# versao1.net
KiCad netlist of a schematic drawn in EAGLE
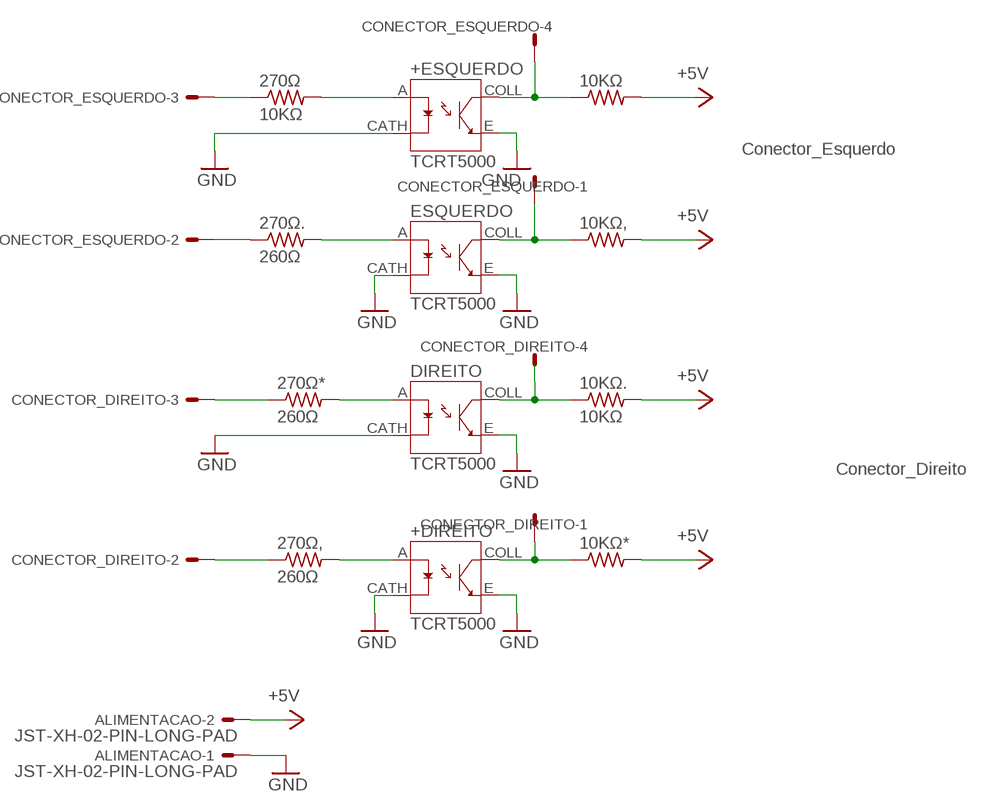
[diagram p0: schematic, sheet 1]

(export (version "E")
  (design (tool "Eeschema 10.0.6"))
  (components
    (comp (ref "+DIREITO")
      (value "TCRT5000")
      (footprint "eagle-import:OPTO_TCRT5000")
      (fields (field (name "MF") "Vishay"))
      (libsource (lib "eagle-import") (part "TCRT5000"))
    )
    (comp (ref "+ESQUERDO")
      (value "TCRT5000")
      (footprint "eagle-import:OPTO_TCRT5000")
      (fields (field (name "MF") "Vishay"))
      (libsource (lib "eagle-import") (part "TCRT5000"))
    )
    (comp (ref "10KΩ")
      (value "R-US_0204/7")
      (footprint "eagle-import:0204_7")
      (libsource (lib "eagle-import") (part "R-US_0204/7"))
    )
    (comp (ref "10KΩ*")
      (value "R-US_0204/7")
      (footprint "eagle-import:0204_7")
      (libsource (lib "eagle-import") (part "R-US_0204/7"))
    )
    (comp (ref "10KΩ,")
      (value "R-US_0204/7")
      (footprint "eagle-import:0204_7")
      (libsource (lib "eagle-import") (part "R-US_0204/7"))
    )
    (comp (ref "10KΩ.")
      (value "10KΩ")
      (footprint "eagle-import:0204_7")
      (libsource (lib "eagle-import") (part "R-US_0204/7"))
    )
    (comp (ref "270Ω")
      (value "10KΩ")
      (footprint "eagle-import:0204_7")
      (libsource (lib "eagle-import") (part "R-US_0204/7"))
    )
    (comp (ref "270Ω*")
      (value "260Ω")
      (footprint "eagle-import:0204_7")
      (libsource (lib "eagle-import") (part "R-US_0204/7"))
    )
    (comp (ref "270Ω,")
      (value "260Ω")
      (footprint "eagle-import:0204_7")
      (libsource (lib "eagle-import") (part "R-US_0204/7"))
    )
    (comp (ref "270Ω.")
      (value "260Ω")
      (footprint "eagle-import:0204_7")
      (libsource (lib "eagle-import") (part "R-US_0204/7"))
    )
    (comp (ref "ALIMENTACAO")
      (value "JST-XH-02-PIN-LONG-PAD")
      (footprint "eagle-import:JST-XH-02-PACKAGE-LONG-PAD")
      (libsource (lib "eagle-import") (part "JST-XH-02-PIN-LONG-PAD"))
    )
    (comp (ref "CONECTOR_DIREITO")
      (value "Conector_Direito")
      (footprint "eagle-import:JST-XH-04-PACKAGE-LONG-PAD")
      (libsource (lib "eagle-import") (part "JST-XH-04-PIN-LONG-PAD"))
    )
    (comp (ref "CONECTOR_ESQUERDO")
      (value "Conector_Esquerdo")
      (footprint "eagle-import:JST-XH-04-PACKAGE-LONG-PAD")
      (libsource (lib "eagle-import") (part "JST-XH-04-PIN-LONG-PAD"))
    )
    (comp (ref "DIREITO")
      (value "TCRT5000")
      (footprint "eagle-import:OPTO_TCRT5000")
      (fields (field (name "MF") "Vishay"))
      (libsource (lib "eagle-import") (part "TCRT5000"))
    )
    (comp (ref "ESQUERDO")
      (value "TCRT5000")
      (footprint "eagle-import:OPTO_TCRT5000")
      (fields (field (name "MF") "Vishay"))
      (libsource (lib "eagle-import") (part "TCRT5000"))
    )
  )
  (nets
    (net (code "1") (name "+5V") (class "Default")
      (node (ref "10KΩ") (pin "2") (pinfunction "2_2") (pintype "passive"))
      (node (ref "10KΩ*") (pin "2") (pinfunction "2_2") (pintype "passive"))
      (node (ref "10KΩ,") (pin "2") (pinfunction "2_2") (pintype "passive"))
      (node (ref "10KΩ.") (pin "2") (pinfunction "2_2") (pintype "passive"))
      (node (ref "ALIMENTACAO") (pin "2") (pinfunction "S_2") (pintype "passive"))
    )
    (net (code "2") (name "GND") (class "Default")
      (node (ref "+DIREITO") (pin "CATH") (pinfunction "CATH_CATH") (pintype "passive"))
      (node (ref "+DIREITO") (pin "E") (pinfunction "E_E") (pintype "passive"))
      (node (ref "+ESQUERDO") (pin "CATH") (pinfunction "CATH_CATH") (pintype "passive"))
      (node (ref "+ESQUERDO") (pin "E") (pinfunction "E_E") (pintype "passive"))
      (node (ref "ALIMENTACAO") (pin "1") (pinfunction "S_1") (pintype "passive"))
      (node (ref "DIREITO") (pin "CATH") (pinfunction "CATH_CATH") (pintype "passive"))
      (node (ref "DIREITO") (pin "E") (pinfunction "E_E") (pintype "passive"))
      (node (ref "ESQUERDO") (pin "CATH") (pinfunction "CATH_CATH") (pintype "passive"))
      (node (ref "ESQUERDO") (pin "E") (pinfunction "E_E") (pintype "passive"))
    )
    (net (code "3") (name "Net-(+DIREITO-PadA)") (class "Default")
      (node (ref "+DIREITO") (pin "A") (pinfunction "A_A") (pintype "passive"))
      (node (ref "270Ω,") (pin "2") (pinfunction "2_2") (pintype "passive"))
    )
    (net (code "4") (name "Net-(+ESQUERDO-PadA)") (class "Default")
      (node (ref "+ESQUERDO") (pin "A") (pinfunction "A_A") (pintype "passive"))
      (node (ref "270Ω") (pin "2") (pinfunction "2_2") (pintype "passive"))
    )
    (net (code "5") (name "Net-(270Ω*-Pad2)") (class "Default")
      (node (ref "270Ω*") (pin "2") (pinfunction "2_2") (pintype "passive"))
      (node (ref "DIREITO") (pin "A") (pinfunction "A_A") (pintype "passive"))
    )
    (net (code "6") (name "Net-(270Ω.-Pad2)") (class "Default")
      (node (ref "270Ω.") (pin "2") (pinfunction "2_2") (pintype "passive"))
      (node (ref "ESQUERDO") (pin "A") (pinfunction "A_A") (pintype "passive"))
    )
    (net (code "7") (name "Net-(CONECTOR_DIREITOA-S)") (class "Default")
      (node (ref "+DIREITO") (pin "COLL") (pinfunction "COLL_COLL") (pintype "passive"))
      (node (ref "10KΩ*") (pin "1") (pinfunction "1_1") (pintype "passive"))
      (node (ref "CONECTOR_DIREITO") (pin "1") (pinfunction "S_1") (pintype "passive"))
    )
    (net (code "8") (name "Net-(CONECTOR_DIREITOB-S)") (class "Default")
      (node (ref "270Ω,") (pin "1") (pinfunction "1_1") (pintype "passive"))
      (node (ref "CONECTOR_DIREITO") (pin "2") (pinfunction "S_2") (pintype "passive"))
    )
    (net (code "9") (name "Net-(CONECTOR_DIREITOC-S)") (class "Default")
      (node (ref "270Ω*") (pin "1") (pinfunction "1_1") (pintype "passive"))
      (node (ref "CONECTOR_DIREITO") (pin "3") (pinfunction "S_3") (pintype "passive"))
    )
    (net (code "10") (name "Net-(CONECTOR_DIREITOD-S)") (class "Default")
      (node (ref "10KΩ.") (pin "1") (pinfunction "1_1") (pintype "passive"))
      (node (ref "CONECTOR_DIREITO") (pin "4") (pinfunction "S_4") (pintype "passive"))
      (node (ref "DIREITO") (pin "COLL") (pinfunction "COLL_COLL") (pintype "passive"))
    )
    (net (code "11") (name "Net-(CONECTOR_ESQUERDOA-S)") (class "Default")
      (node (ref "10KΩ,") (pin "1") (pinfunction "1_1") (pintype "passive"))
      (node (ref "CONECTOR_ESQUERDO") (pin "1") (pinfunction "S_1") (pintype "passive"))
      (node (ref "ESQUERDO") (pin "COLL") (pinfunction "COLL_COLL") (pintype "passive"))
    )
    (net (code "12") (name "Net-(CONECTOR_ESQUERDOB-S)") (class "Default")
      (node (ref "270Ω.") (pin "1") (pinfunction "1_1") (pintype "passive"))
      (node (ref "CONECTOR_ESQUERDO") (pin "2") (pinfunction "S_2") (pintype "passive"))
    )
    (net (code "13") (name "Net-(CONECTOR_ESQUERDOC-S)") (class "Default")
      (node (ref "270Ω") (pin "1") (pinfunction "1_1") (pintype "passive"))
      (node (ref "CONECTOR_ESQUERDO") (pin "3") (pinfunction "S_3") (pintype "passive"))
    )
    (net (code "14") (name "Net-(CONECTOR_ESQUERDOD-S)") (class "Default")
      (node (ref "+ESQUERDO") (pin "COLL") (pinfunction "COLL_COLL") (pintype "passive"))
      (node (ref "10KΩ") (pin "1") (pinfunction "1_1") (pintype "passive"))
      (node (ref "CONECTOR_ESQUERDO") (pin "4") (pinfunction "S_4") (pintype "passive"))
    )
  )
)
